# Sheet1.net
KiCad netlist of a schematic drawn in Altium Designer
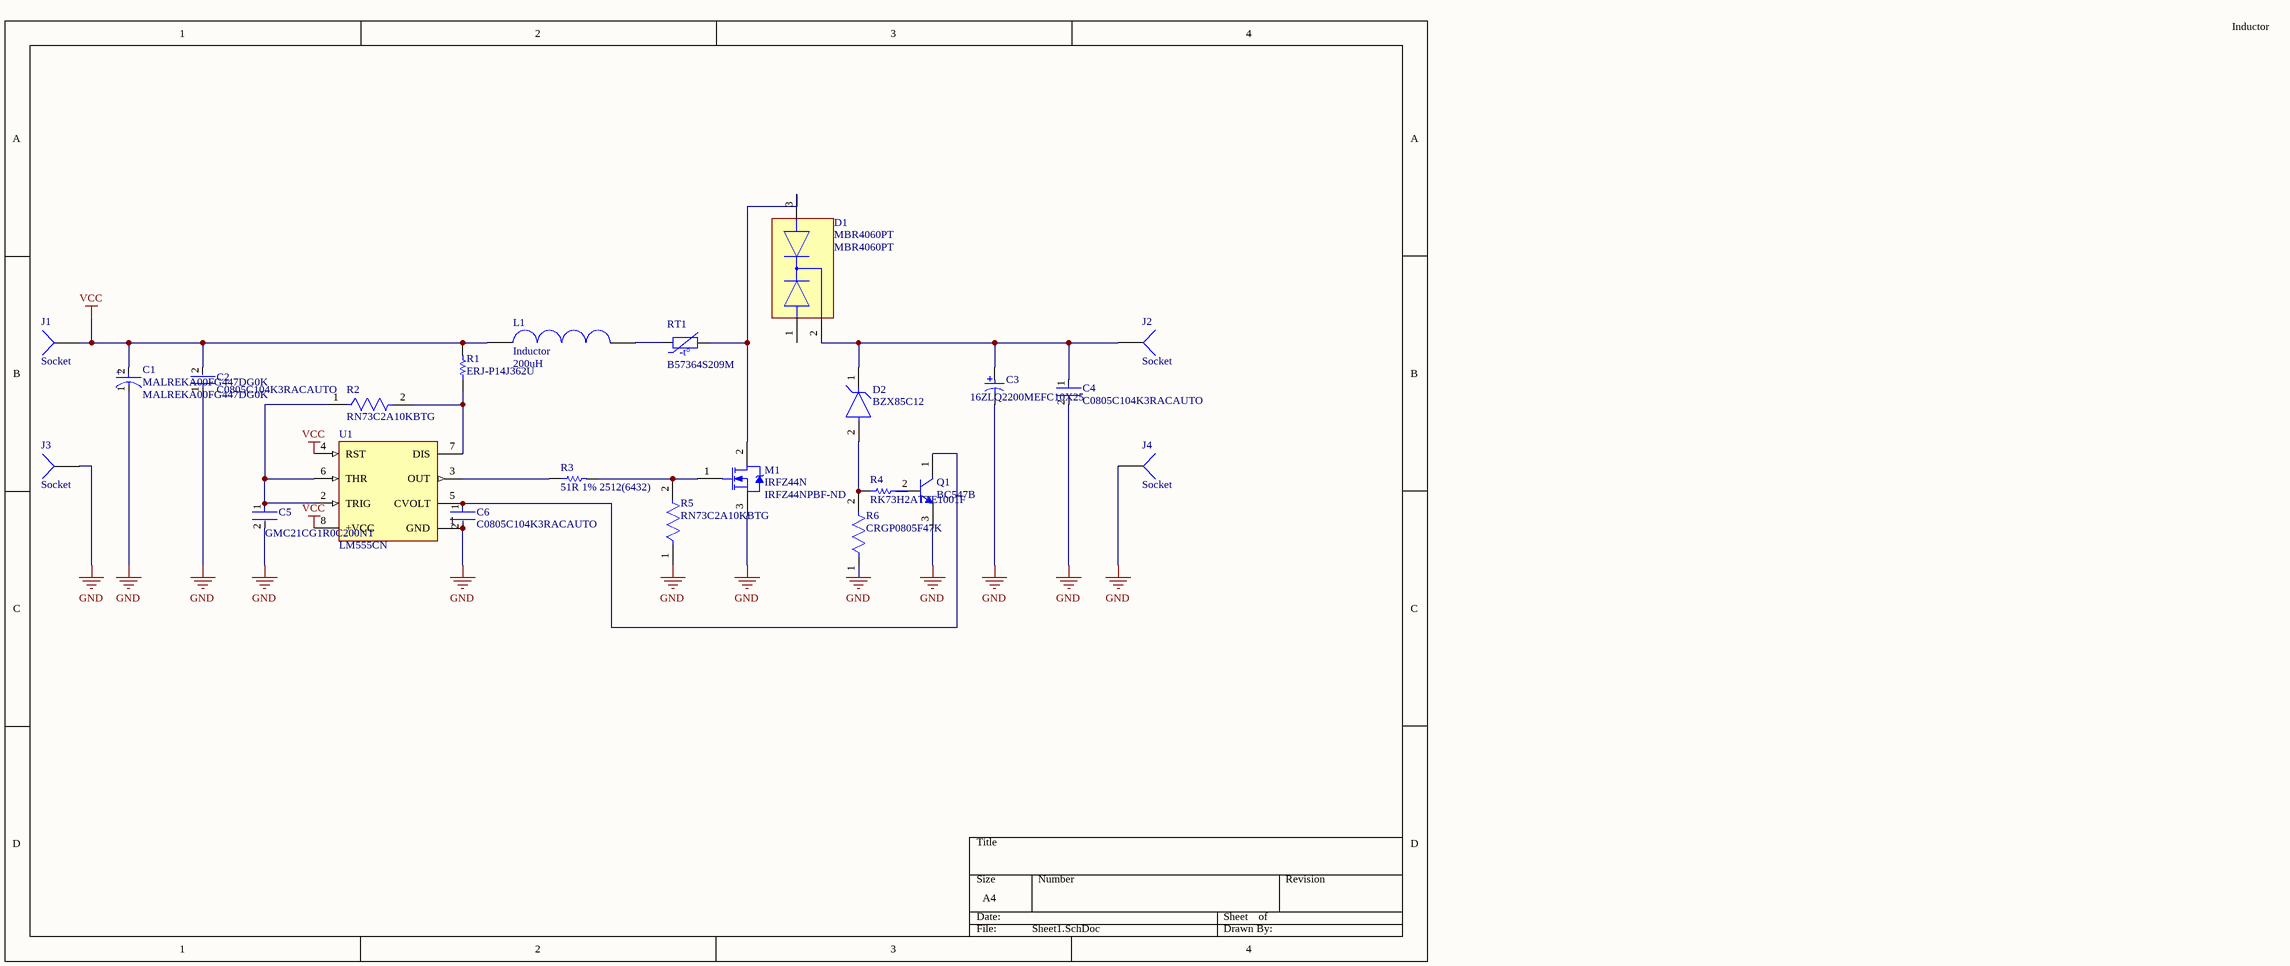
[diagram p0: Sheet1.SchDoc]

(export (version "E")
  (design (tool "Eeschema 10.0.6"))
  (components
    (comp (ref "C1")
      (value "MALREKA00FG447DG0K")
      (footprint "FP-ECA-1HM102-MFG")
      (description "Cap Alum 4700UF 20% 16V Radial")
      (fields
        (field (name "MANUFACTURER") "Vishay Roederstein")
        (field (name "TOLERANCE") "20%")
        (field (name "SUPPLIER PART NUMBER 1") "MALREKA00FG447DG0K")
      )
      (libsource (lib "IRFZ44N_1") (part "MALREKA00FG447DG0K"))
    )
    (comp (ref "C2")
      (value "C0805C104K3RACAUTO")
      (footprint "FP-C0805C-DN-IPC_A")
      (description "CAP CER 0.1UF 25V X7R 0805")
      (fields
        (field (name "MANUFACTURER") "KEMET")
        (field (name "OCTOPART") "https://octopart.com/c0805c104k3racauto-kemet-12542886")
      )
      (libsource (lib "Altium Content Vault") (part "b4654b650e69147ec39a6b967a45e02"))
    )
    (comp (ref "C3")
      (value "16ZLQ2200MEFC10X25")
      (footprint "PNSC-EEUFM1H221-2")
      (description "Cap Aluminum Lytic 2200uF 16V 20% (10 X 25mm) Radial 5mm 2500mA 5000h 105C")
      (fields (field (name "MANUFACTURER") "Rubycon") (field (name "TOLERANCE") "20%"))
      (libsource (lib "IRFZ44N_1") (part "16ZLQ2200MEFC10X25"))
    )
    (comp (ref "C4")
      (value "C0805C104K3RACAUTO")
      (footprint "FP-C0805C-DN-IPC_A")
      (description "CAP CER 0.1UF 25V X7R 0805")
      (fields
        (field (name "MANUFACTURER") "KEMET")
        (field (name "OCTOPART") "https://octopart.com/c0805c104k3racauto-kemet-12542886")
      )
      (libsource (lib "Altium Content Vault") (part "b4654b650e69147ec39a6b967a45e02"))
    )
    (comp (ref "C5")
      (value "GMC21CG1R0C200NT")
      (footprint "FP-C0805C-DN-IPC_A")
      (description "1 pF ±0.25pF 200V Ceramic Capacitor C0G, NP0 0805R 0805")
      (fields
        (field (name "MANUFACTURER") "KEMET")
        (field (name "MANUFACTURER PART NUMBER") "C0805C102K5RACAUTO")
      )
      (libsource (lib "Altium Content Vault") (part "b4654b650e69147ec39a6b967a45e02"))
    )
    (comp (ref "C6")
      (value "C0805C104K3RACAUTO")
      (footprint "FP-C0805C-DN-IPC_A")
      (description "CAP CER 0.1UF 25V X7R 0805")
      (fields
        (field (name "MANUFACTURER") "KEMET")
        (field (name "OCTOPART") "https://octopart.com/c0805c104k3racauto-kemet-12542886")
      )
      (libsource (lib "Altium Content Vault") (part "b4654b650e69147ec39a6b967a45e02"))
    )
    (comp (ref "D1")
      (value "MBR4060PT")
      (footprint "FP-340BZ-MFG")
      (description "Schottky Diodes & Rectifiers 43 amp Rectifiers Schottky Barrier")
      (fields
        (field (name "MANUFACTURER") "ON Semiconductor / Fairchild")
        (field (name "SUPPLIER PART NUMBER 1") "MBR4060PT")
      )
      (libsource (lib "IRFZ44N_1") (part "MBR4060PT"))
    )
    (comp (ref "D2")
      (value "BZX85C12")
      (footprint "FP-017AH-MFG")
      (description "DIODE ZENER 12V 1W DO41")
      (fields
        (field (name "MANUFACTURER") "ON Semiconductor")
        (field (name "OCTOPART") "https://octopart.com/bzx85c12-on+semiconductor-84409056")
      )
      (libsource (lib "Altium Content Vault") (part "f813f71cba58e380607f5dd3caf9714"))
    )
    (comp (ref "J1")
      (value "Socket")
      (footprint "PIN1")
      (fields (field (name "PUBLISHER") "Altium Limited"))
      (libsource (lib "Miscellaneous Connectors") (part "Socket"))
    )
    (comp (ref "J2")
      (value "Socket")
      (footprint "PIN1")
      (fields (field (name "PUBLISHER") "Altium Limited"))
      (libsource (lib "Miscellaneous Connectors") (part "Socket"))
    )
    (comp (ref "J3")
      (value "Socket")
      (footprint "PIN1")
      (fields (field (name "PUBLISHER") "Altium Limited"))
      (libsource (lib "Miscellaneous Connectors") (part "Socket"))
    )
    (comp (ref "J4")
      (value "Socket")
      (footprint "PIN1")
      (fields (field (name "PUBLISHER") "Altium Limited"))
      (libsource (lib "Miscellaneous Connectors") (part "Socket"))
    )
    (comp (ref "L1")
      (value "Inductor")
      (footprint "Inductor")
      (fields (field (name "ALTIUM_VALUE") "200uH"))
      (libsource (lib "Inductance") (part "Inductor"))
    )
    (comp (ref "M1")
      (value "IRFZ44N")
      (footprint "INF-PG-TO220-3-1")
      (description "MOSFET, Power; N-Ch; VDSS 55V; RDS(ON) 17.5 Milliohms; ID 49A; TO-220AB; PD 94W; -55deg")
      (fields
        (field (name "MANUFACTURER") "International Rectifier")
        (field (name "SUPPLIER PART NUMBER 1") "IRFZ44NPBF-ND")
      )
      (libsource (lib "IRFZ44N_1") (part "IRFZ44N"))
    )
    (comp (ref "Q1")
      (value "BC547B")
      (footprint "ONSC-TO-92-3-29-11")
      (description "Amplifier Transistor, NPN Silicon, 3-Pin TO-92, Bulk Box")
      (fields (field (name "MANUFACTURER") "On Semiconductor"))
      (libsource (lib "Altium Content Vault") (part "ONSC-NPN-C1B2E3-3"))
    )
    (comp (ref "R1")
      (value "ERJ-P14J362U")
      (footprint "RESC3225X70X50ML20T20")
      (fields (field (name "MANUFACTURER") "Panasonic"))
      (libsource (lib "Altium Content Vault") (part "RES"))
    )
    (comp (ref "R2")
      (value "RN73C2A10KBTG")
      (footprint "FP-RN732A-IPC_A")
      (description "SMD Chip Resistor, Thin Film, 10KΩ, 100 V, 0805 [2012 Metric], 100 mW, 0.1%, RN73 Series")
      (fields (field (name "MANUFACTURER") "TE Connectivity") (field (name "TOLERANCE") "0.1%"))
      (libsource (lib "Altium Content Vault") (part "1029c3af85768c4190bb7ad29bc67b5"))
    )
    (comp (ref "R3")
      (value "51R 1% 2512(6432)")
      (footprint "RESC2512(6432)_M")
      (description "51R 1W 1% 2512 (6432 Metric)  SMD")
      (fields (field (name "TOLERANCE") "1 %") (field (name "POWER") "1 W"))
      (libsource (lib "Altium Content Vault") (part "RES"))
    )
    (comp (ref "R4")
      (value "RK73H2ATTE1001F")
      (footprint "RESC2013X60X30ML20T20")
      (fields (field (name "MANUFACTURER") "KOA Speer"))
      (libsource (lib "Altium Content Vault") (part "RES"))
    )
    (comp (ref "R5")
      (value "RN73C2A10KBTG")
      (footprint "FP-RN732A-IPC_A")
      (description "SMD Chip Resistor, Thin Film, 10KΩ, 100 V, 0805 [2012 Metric], 100 mW, 0.1%, RN73 Series")
      (fields (field (name "MANUFACTURER") "TE Connectivity") (field (name "TOLERANCE") "0.1%"))
      (libsource (lib "Altium Content Vault") (part "1029c3af85768c4190bb7ad29bc67b5"))
    )
    (comp (ref "R6")
      (value "CRGP0805F47K")
      (footprint "FP-CRGP0805-IPC_A")
      (description "CRGP0805 47KΩ 0.33W ±100ppm/°C 1% 150V")
      (fields (field (name "MANUFACTURER") "TE") (field (name "TOLERANCE") "0.01"))
      (libsource (lib "Altium Content Vault") (part "1029c3af85768c4190bb7ad29bc67b5"))
    )
    (comp (ref "RT1")
      (value "B57364S209M")
      (footprint "TDK-B57364")
      (description "Inrush Current Limiter, 2 Ohm, -55 to 170 degC, 2-Pin THD, RoHS, Bulk")
      (fields (field (name "MANUFACTURER") "TDK"))
      (libsource (lib "Altium Content Vault") (part "RES-NTC-2"))
    )
    (comp (ref "U1")
      (value "LM555CN")
      (footprint "N08E")
      (description "Timer, 8-pin MDIP")
      (fields (field (name "MANUFACTURER") "National Semiconductor"))
      (libsource (lib "Altium Content Vault") (part "AN-TIMER-LM555-8"))
    )
  )
  (nets
    (net (code "1") (name "GND") (class "Default")
      (node (ref "C1") (pin "1") (pinfunction "C_1") (pintype "passive"))
      (node (ref "C2") (pin "1") (pinfunction "1_1") (pintype "passive"))
      (node (ref "C3") (pin "2") (pinfunction "2_2") (pintype "passive"))
      (node (ref "C4") (pin "2") (pinfunction "2_2") (pintype "passive"))
      (node (ref "C5") (pin "2") (pinfunction "2_2") (pintype "passive"))
      (node (ref "C6") (pin "2") (pinfunction "2_2") (pintype "passive"))
      (node (ref "J3") (pin "1") (pinfunction "1_1") (pintype "passive"))
      (node (ref "J4") (pin "1") (pinfunction "1_1") (pintype "passive"))
      (node (ref "M1") (pin "3") (pinfunction "SOURCE_3") (pintype "passive"))
      (node (ref "Q1") (pin "3") (pinfunction "E_3") (pintype "passive"))
      (node (ref "R5") (pin "1") (pinfunction "1_1") (pintype "passive"))
      (node (ref "R6") (pin "1") (pinfunction "1_1") (pintype "passive"))
      (node (ref "U1") (pin "1") (pinfunction "GND_1") (pintype "power_in"))
    )
    (net (code "2") (name "Net-(D1-2_ANODE)") (class "Default")
      (node (ref "D1") (pin "3") (pinfunction "2_ANODE_3") (pintype "passive"))
      (node (ref "M1") (pin "2") (pinfunction "DRAIN_2") (pintype "passive"))
      (node (ref "RT1") (pin "1") (pinfunction "1_1") (pintype "passive"))
    )
    (net (code "3") (name "Net-(D1-COMMON_CATHODE)") (class "Default")
      (node (ref "C3") (pin "1") (pinfunction "1_1") (pintype "passive"))
      (node (ref "C4") (pin "1") (pinfunction "1_1") (pintype "passive"))
      (node (ref "D1") (pin "2") (pinfunction "COMMON_CATHODE_2") (pintype "passive"))
      (node (ref "D2") (pin "1") (pinfunction "C_1") (pintype "passive"))
      (node (ref "J2") (pin "1") (pinfunction "1_1") (pintype "passive"))
    )
    (net (code "4") (name "Net-(D2-A)") (class "Default")
      (node (ref "D2") (pin "2") (pinfunction "A_2") (pintype "passive"))
      (node (ref "R4") (pin "1") (pinfunction "1_1") (pintype "passive"))
      (node (ref "R6") (pin "2") (pinfunction "2_2") (pintype "passive"))
    )
    (net (code "5") (name "Net-(L1-Pad1)") (class "Default")
      (node (ref "L1") (pin "1") (pintype "passive"))
      (node (ref "RT1") (pin "2") (pinfunction "2_2") (pintype "passive"))
    )
    (net (code "6") (name "Net-(M1-GATE)") (class "Default")
      (node (ref "M1") (pin "1") (pinfunction "GATE_1") (pintype "passive"))
      (node (ref "R3") (pin "2") (pinfunction "2_2") (pintype "passive"))
      (node (ref "R5") (pin "2") (pinfunction "2_2") (pintype "passive"))
    )
    (net (code "7") (name "Net-(Q1-B)") (class "Default")
      (node (ref "Q1") (pin "2") (pinfunction "B_2") (pintype "passive"))
      (node (ref "R4") (pin "2") (pinfunction "2_2") (pintype "passive"))
    )
    (net (code "8") (name "Net-(Q1-C)") (class "Default")
      (node (ref "C6") (pin "1") (pinfunction "1_1") (pintype "passive"))
      (node (ref "Q1") (pin "1") (pinfunction "C_1") (pintype "passive"))
      (node (ref "U1") (pin "5") (pinfunction "CVOLT_5") (pintype "passive"))
    )
    (net (code "9") (name "Net-(U1-DIS)") (class "Default")
      (node (ref "R1") (pin "1") (pinfunction "1_1") (pintype "passive"))
      (node (ref "R2") (pin "2") (pinfunction "2_2") (pintype "passive"))
      (node (ref "U1") (pin "7") (pinfunction "DIS_7") (pintype "open_collector"))
    )
    (net (code "10") (name "Net-(U1-OUT)") (class "Default")
      (node (ref "R3") (pin "1") (pinfunction "1_1") (pintype "passive"))
      (node (ref "U1") (pin "3") (pinfunction "OUT_3") (pintype "output"))
    )
    (net (code "11") (name "Net-(U1-THR)") (class "Default")
      (node (ref "C5") (pin "1") (pinfunction "1_1") (pintype "passive"))
      (node (ref "R2") (pin "1") (pinfunction "1_1") (pintype "passive"))
      (node (ref "U1") (pin "2") (pinfunction "TRIG_2") (pintype "input"))
      (node (ref "U1") (pin "6") (pinfunction "THR_6") (pintype "input"))
    )
    (net (code "12") (name "VCC") (class "Default")
      (node (ref "C1") (pin "2") (pinfunction "A_2") (pintype "passive"))
      (node (ref "C2") (pin "2") (pinfunction "2_2") (pintype "passive"))
      (node (ref "J1") (pin "1") (pinfunction "1_1") (pintype "passive"))
      (node (ref "L1") (pin "2") (pintype "passive"))
      (node (ref "R1") (pin "2") (pinfunction "2_2") (pintype "passive"))
      (node (ref "U1") (pin "4") (pinfunction "RST_4") (pintype "input"))
      (node (ref "U1") (pin "8") (pinfunction "+VCC_8") (pintype "power_in"))
    )
    (net (code "13") (name "unconnected-(D1-1_ANODE-Pad1)") (class "Default")
      (node (ref "D1") (pin "1") (pinfunction "1_ANODE_1") (pintype "passive"))
    )
  )
)
